# module_Rx_mux.net
KiCad netlist of a schematic drawn in EAGLE
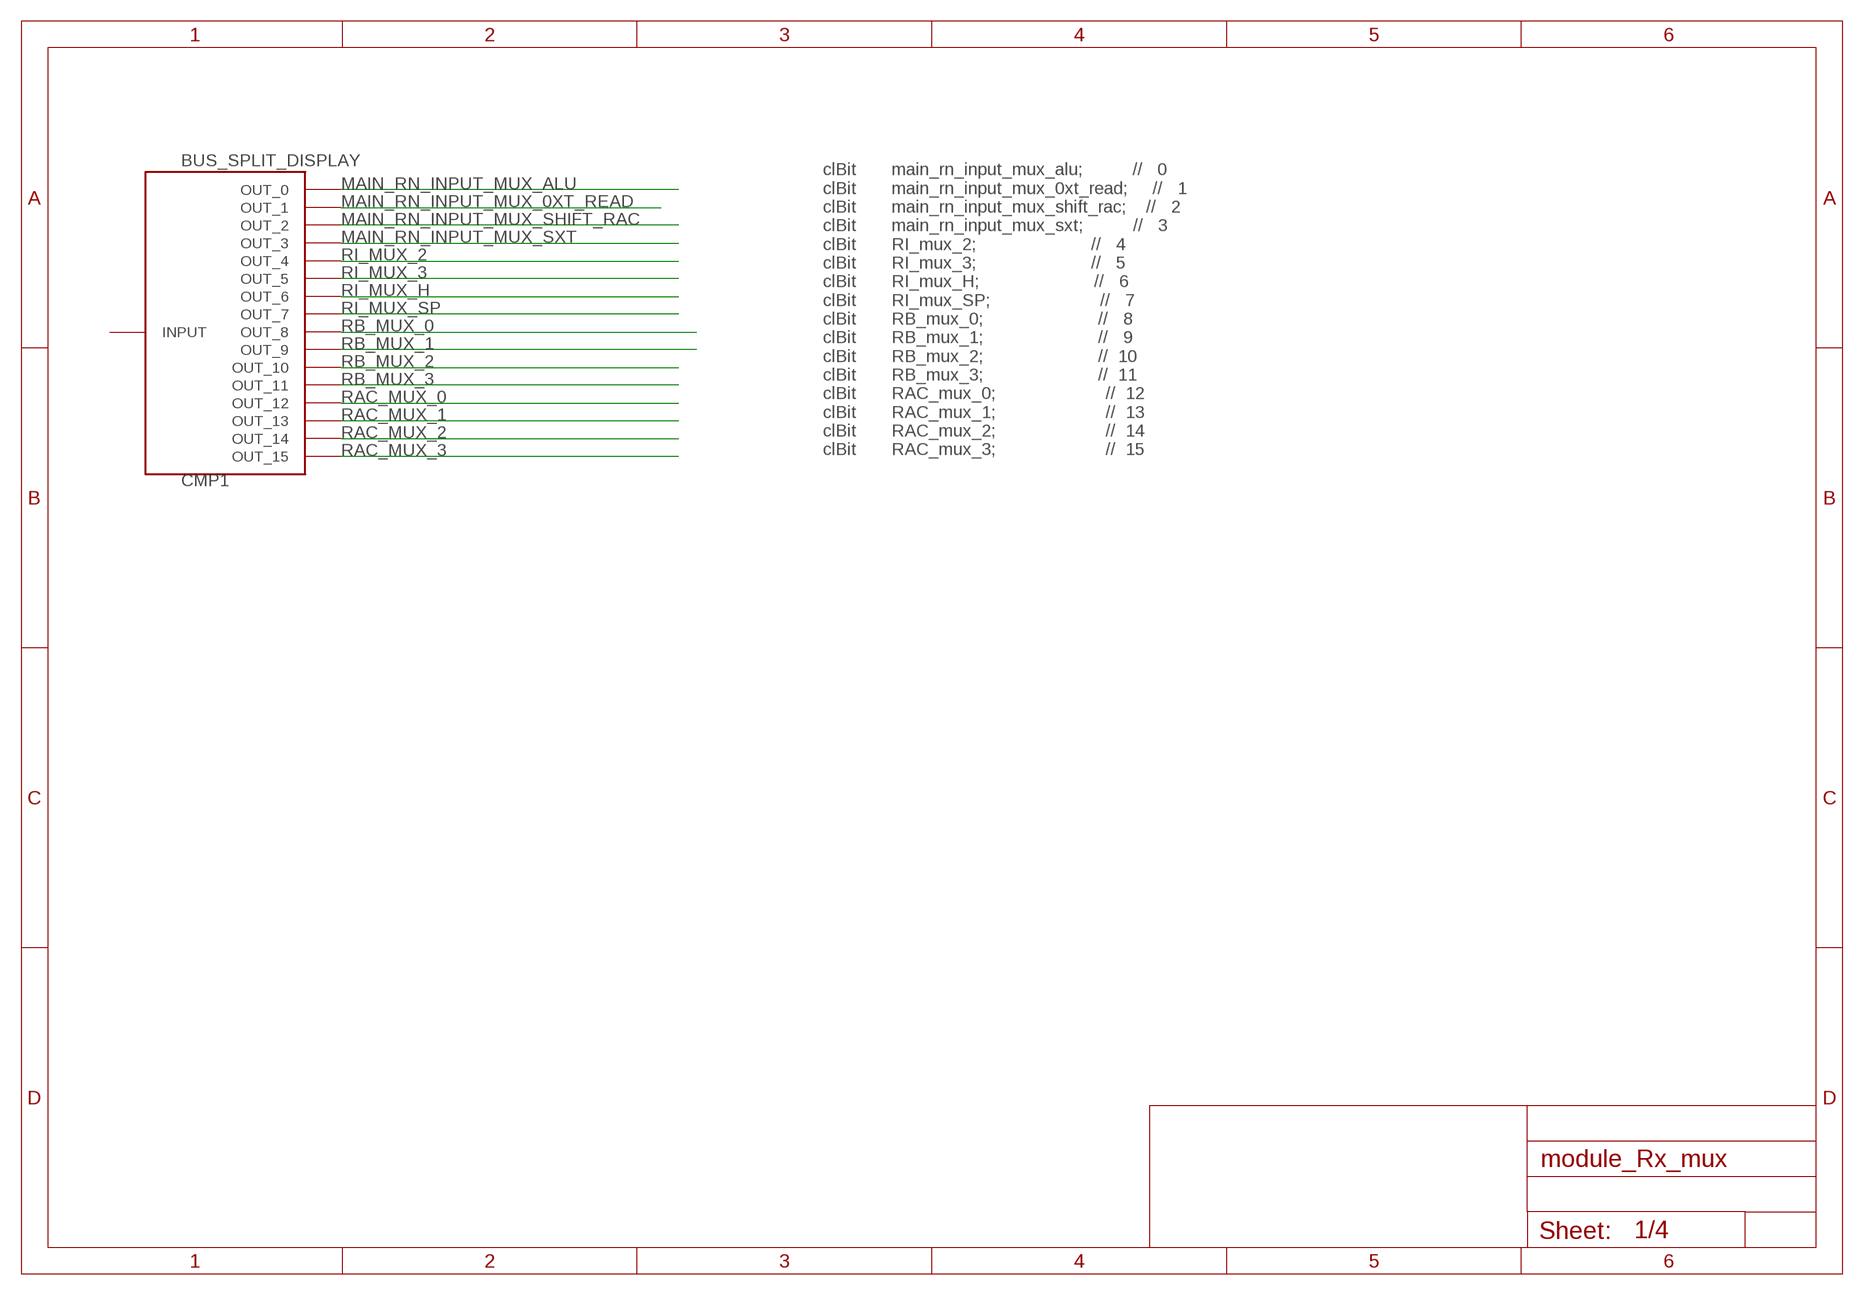
[diagram p0: schematic, sheet 1]
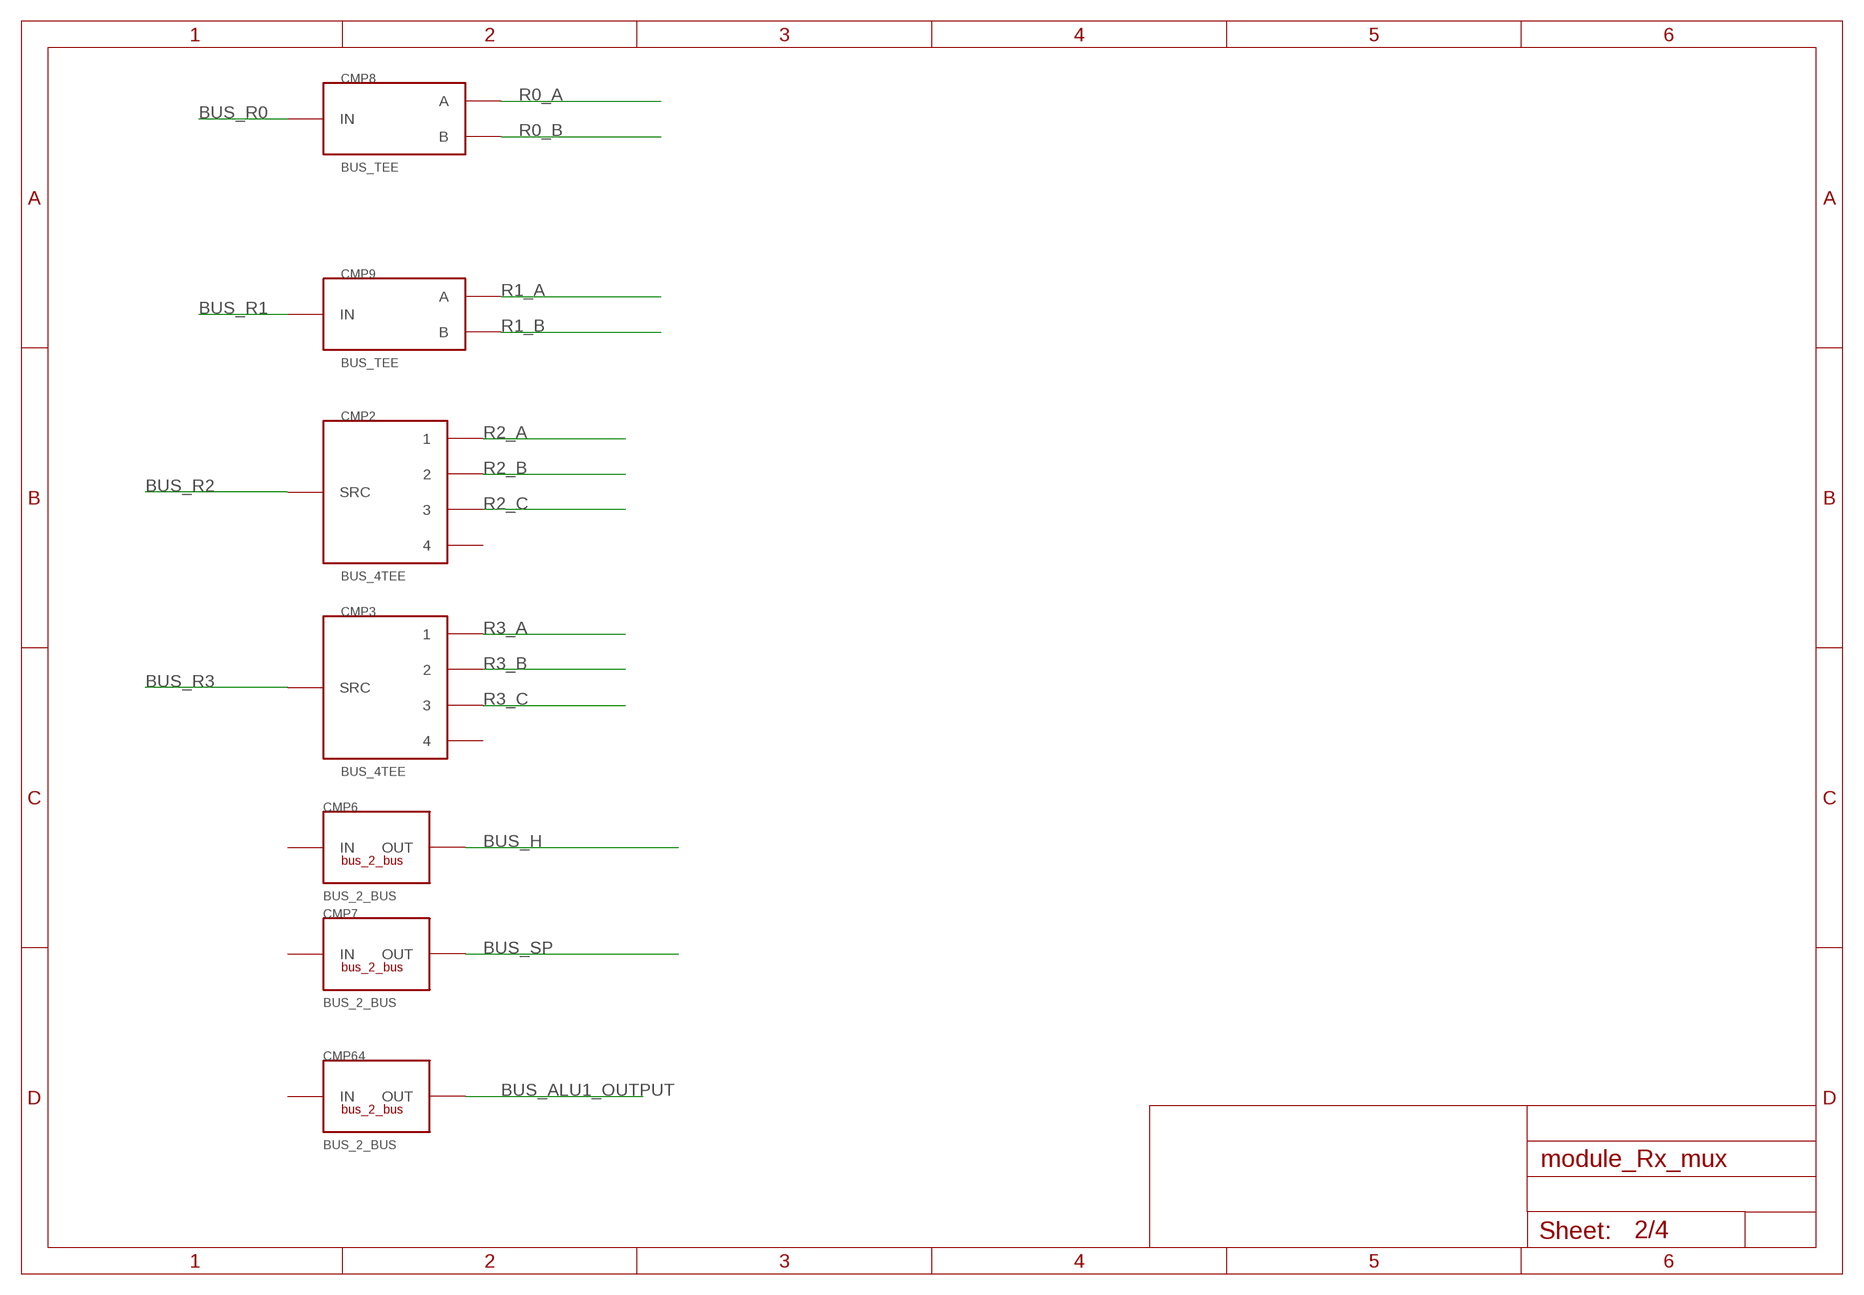
[diagram p1: schematic, sheet 2]
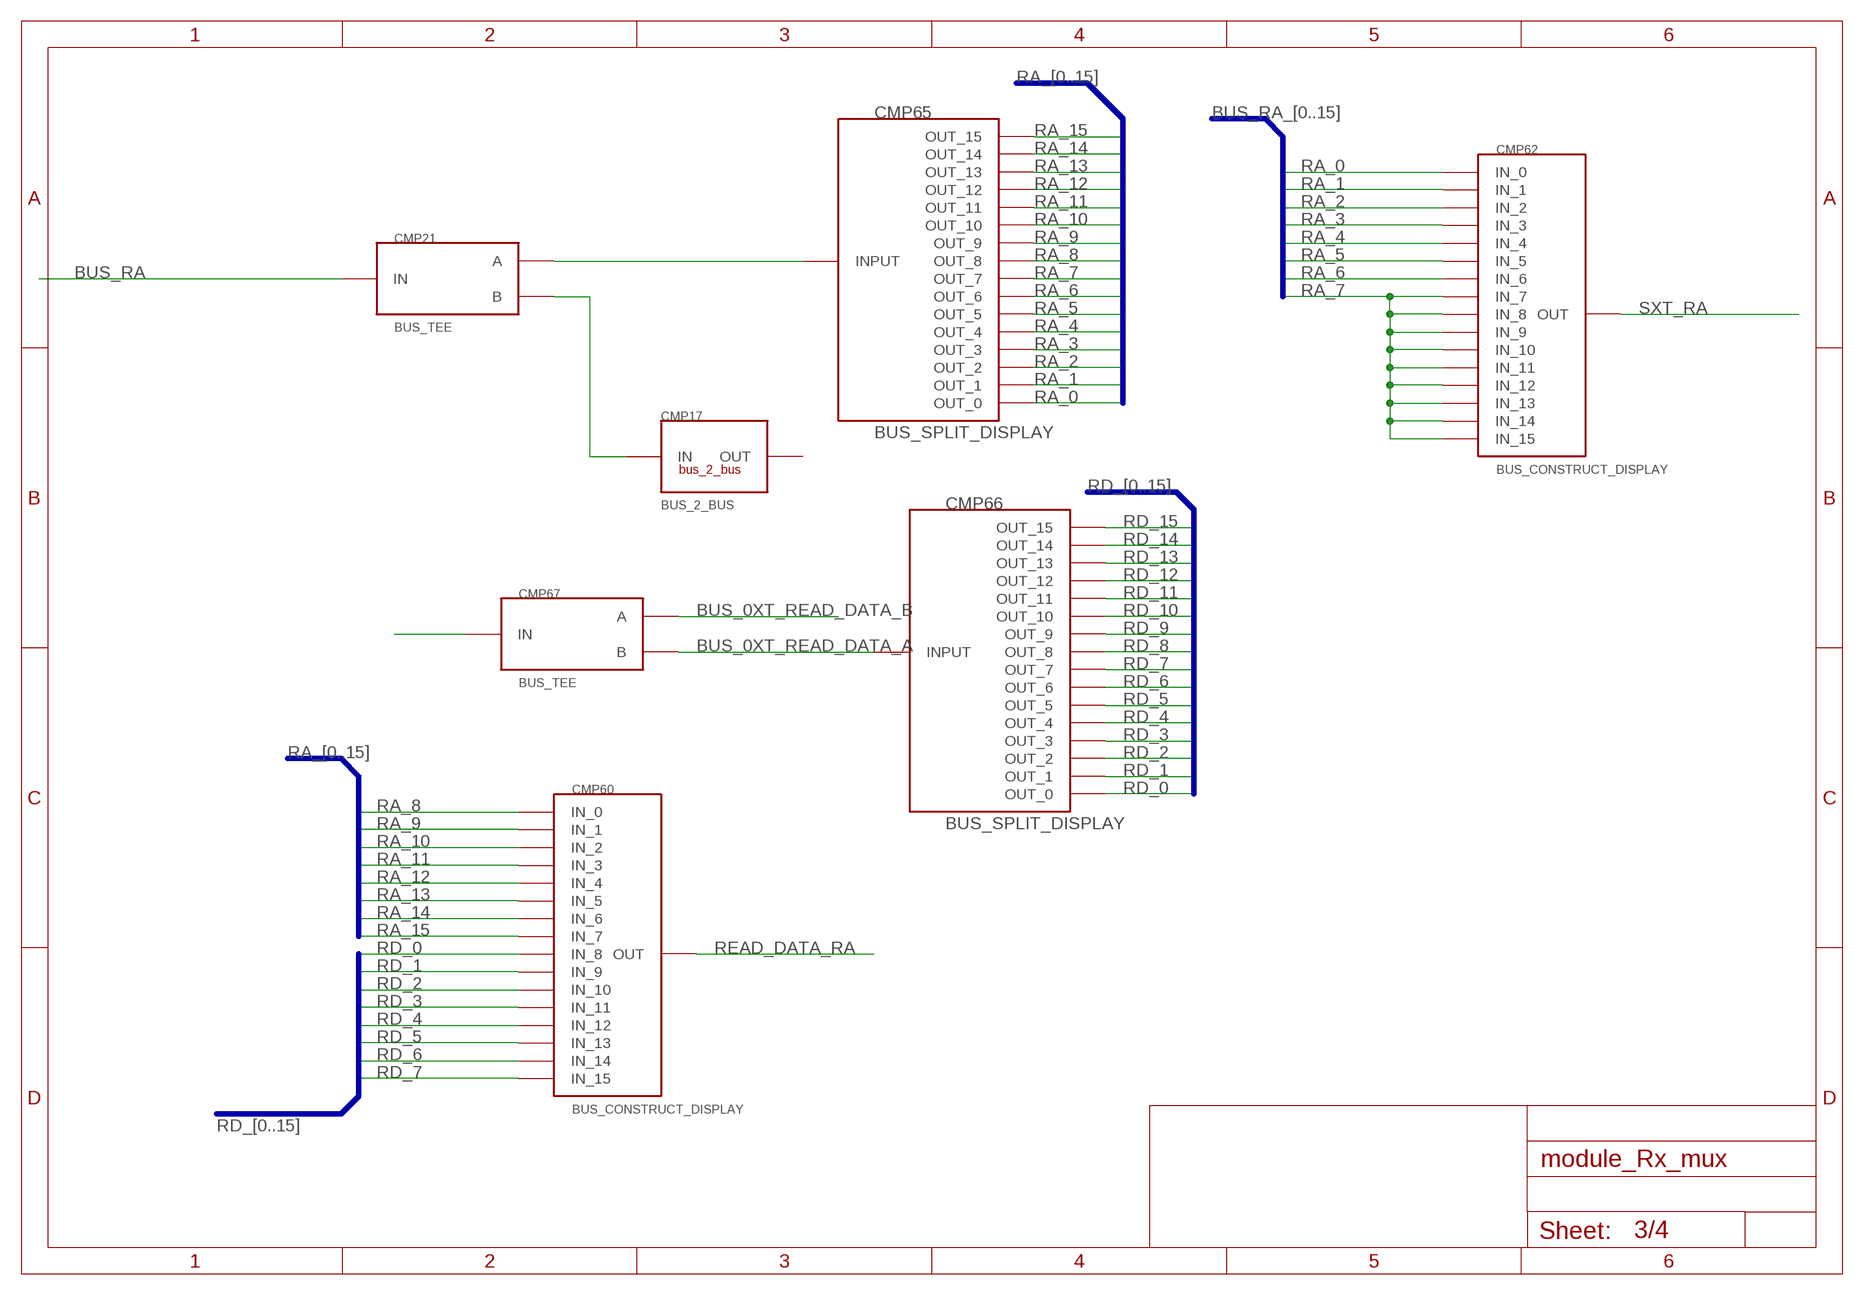
[diagram p2: schematic, sheet 3]
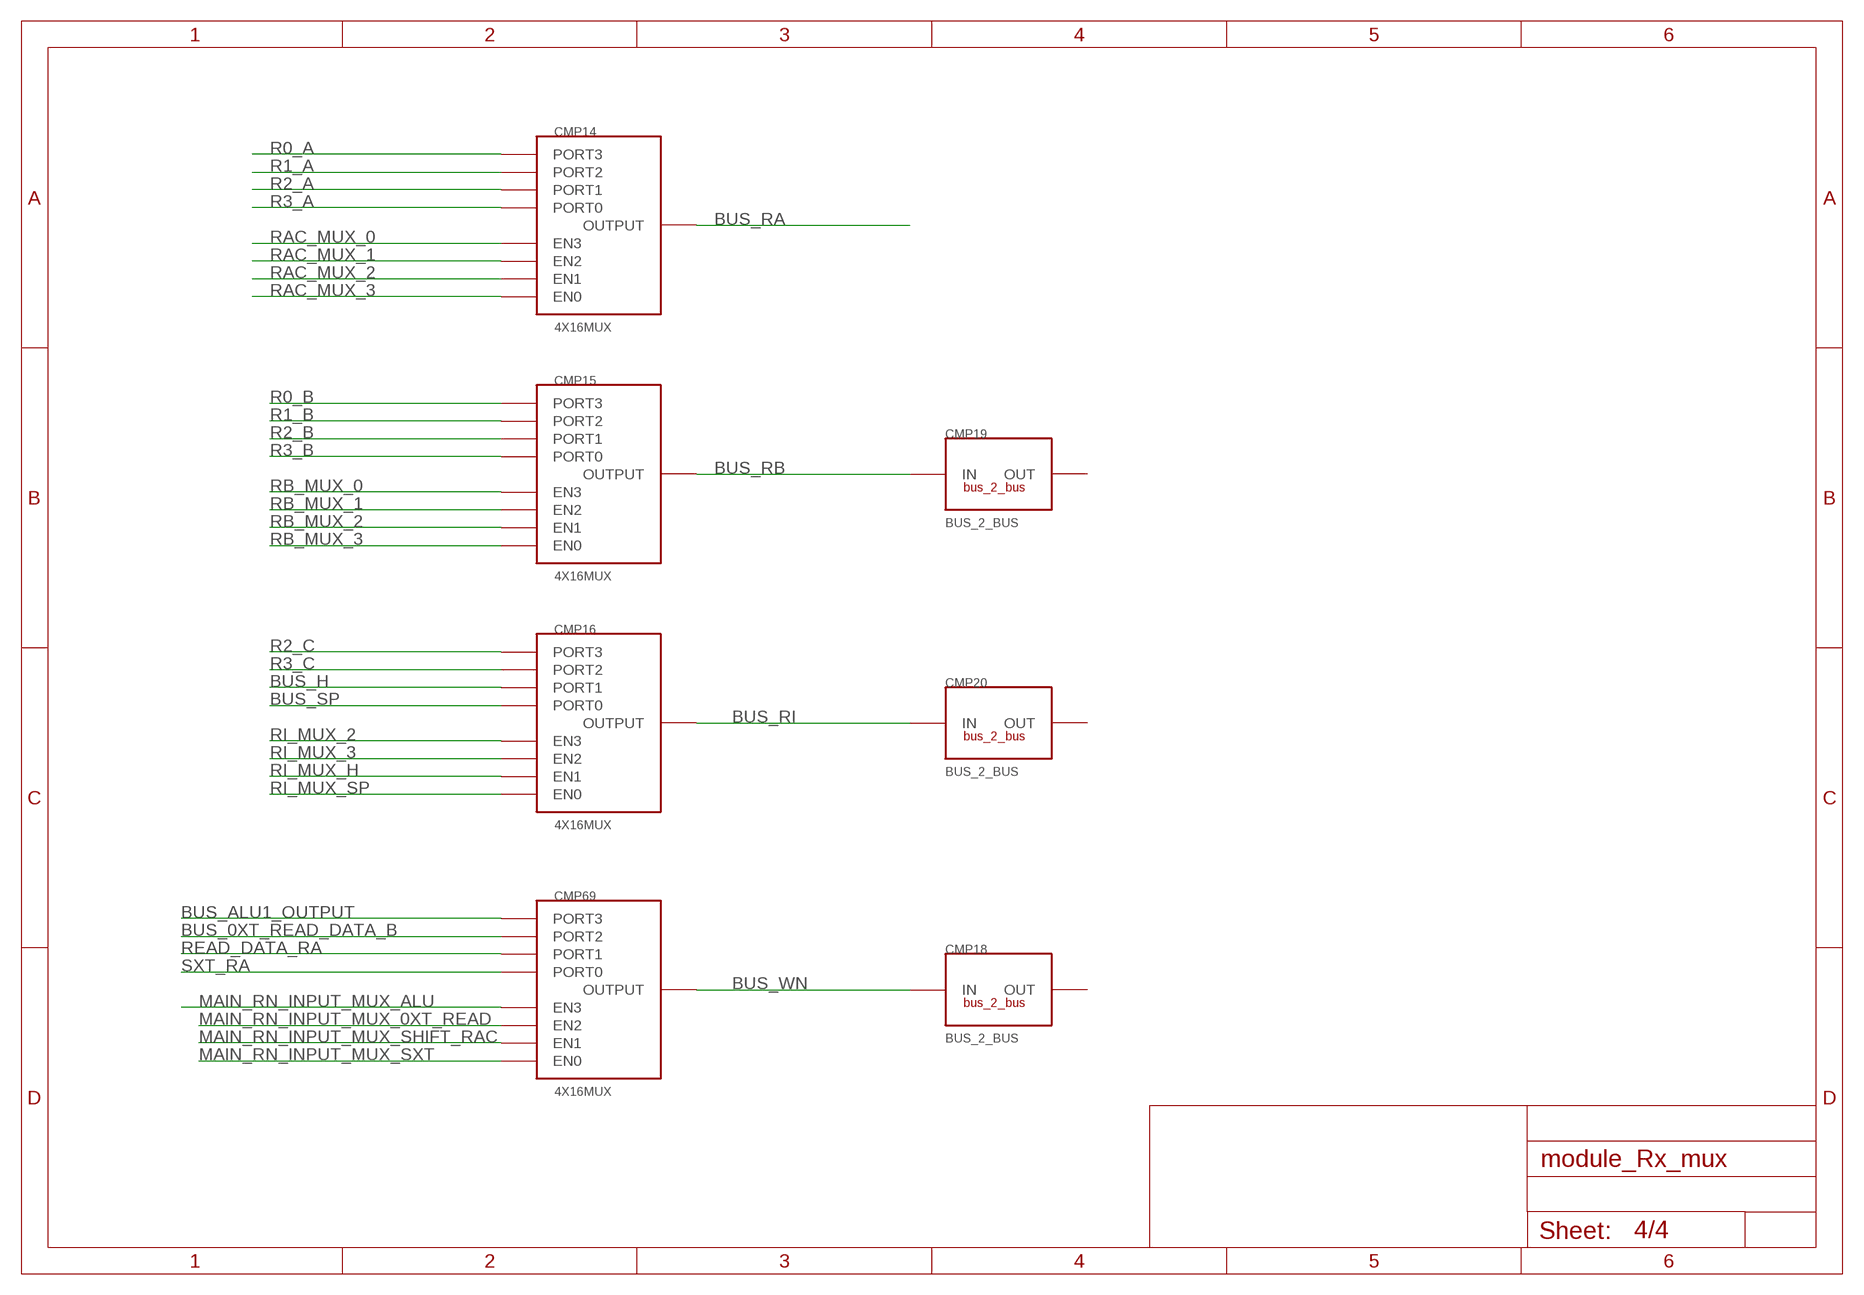
[diagram p3: schematic, sheet 4]

(export (version "E")
  (design (tool "Eeschema 10.0.6"))
  (components
    (comp (ref "CMP2")
      (value "BUS_4TEE")
      (footprint "eagle-import:BUS_4TEE")
      (libsource (lib "eagle-import") (part "BUS_4TEE"))
    )
    (comp (ref "CMP3")
      (value "BUS_4TEE")
      (footprint "eagle-import:BUS_4TEE")
      (libsource (lib "eagle-import") (part "BUS_4TEE"))
    )
    (comp (ref "CMP6")
      (value "BUS_2_BUS")
      (footprint "eagle-import:BUS2BUS")
      (libsource (lib "eagle-import") (part "BUS_2_BUS"))
    )
    (comp (ref "CMP7")
      (value "BUS_2_BUS")
      (footprint "eagle-import:BUS2BUS")
      (libsource (lib "eagle-import") (part "BUS_2_BUS"))
    )
    (comp (ref "CMP8")
      (value "BUS_TEE")
      (footprint "eagle-import:BUS_TEE")
      (libsource (lib "eagle-import") (part "BUS_TEE"))
    )
    (comp (ref "CMP9")
      (value "BUS_TEE")
      (footprint "eagle-import:BUS_TEE")
      (libsource (lib "eagle-import") (part "BUS_TEE"))
    )
    (comp (ref "CMP64")
      (value "BUS_2_BUS")
      (footprint "eagle-import:BUS2BUS")
      (libsource (lib "eagle-import") (part "BUS_2_BUS"))
    )
    (comp (ref "CMP17")
      (value "BUS_2_BUS")
      (footprint "eagle-import:BUS2BUS")
      (libsource (lib "eagle-import") (part "BUS_2_BUS"))
    )
    (comp (ref "CMP21")
      (value "BUS_TEE")
      (footprint "eagle-import:BUS_TEE")
      (libsource (lib "eagle-import") (part "BUS_TEE"))
    )
    (comp (ref "CMP60")
      (value "BUS_CONSTRUCT_DISPLAY")
      (footprint "eagle-import:BUS_SPLIT_DISPLAY")
      (libsource (lib "eagle-import") (part "BUS_CONSTRUCT_DISPLAY"))
    )
    (comp (ref "CMP62")
      (value "BUS_CONSTRUCT_DISPLAY")
      (footprint "eagle-import:BUS_SPLIT_DISPLAY")
      (libsource (lib "eagle-import") (part "BUS_CONSTRUCT_DISPLAY"))
    )
    (comp (ref "CMP65")
      (value "BUS_SPLIT_DISPLAY")
      (footprint "eagle-import:BUS_SPLIT_DISPLAY")
      (libsource (lib "eagle-import") (part "BUS_SPLIT_DISPLAY"))
    )
    (comp (ref "CMP66")
      (value "BUS_SPLIT_DISPLAY")
      (footprint "eagle-import:BUS_SPLIT_DISPLAY")
      (libsource (lib "eagle-import") (part "BUS_SPLIT_DISPLAY"))
    )
    (comp (ref "CMP67")
      (value "BUS_TEE")
      (footprint "eagle-import:BUS_TEE")
      (libsource (lib "eagle-import") (part "BUS_TEE"))
    )
    (comp (ref "CMP1")
      (value "BUS_SPLIT_DISPLAY")
      (footprint "eagle-import:BUS_SPLIT_DISPLAY")
      (libsource (lib "eagle-import") (part "BUS_SPLIT_DISPLAY"))
    )
    (comp (ref "CMP14")
      (value "4X16MUX")
      (footprint "eagle-import:4X16MUX")
      (libsource (lib "eagle-import") (part "4X16MUX"))
    )
    (comp (ref "CMP15")
      (value "4X16MUX")
      (footprint "eagle-import:4X16MUX")
      (libsource (lib "eagle-import") (part "4X16MUX"))
    )
    (comp (ref "CMP16")
      (value "4X16MUX")
      (footprint "eagle-import:4X16MUX")
      (libsource (lib "eagle-import") (part "4X16MUX"))
    )
    (comp (ref "CMP18")
      (value "BUS_2_BUS")
      (footprint "eagle-import:BUS2BUS")
      (libsource (lib "eagle-import") (part "BUS_2_BUS"))
    )
    (comp (ref "CMP19")
      (value "BUS_2_BUS")
      (footprint "eagle-import:BUS2BUS")
      (libsource (lib "eagle-import") (part "BUS_2_BUS"))
    )
    (comp (ref "CMP20")
      (value "BUS_2_BUS")
      (footprint "eagle-import:BUS2BUS")
      (libsource (lib "eagle-import") (part "BUS_2_BUS"))
    )
    (comp (ref "CMP69")
      (value "4X16MUX")
      (footprint "eagle-import:4X16MUX")
      (libsource (lib "eagle-import") (part "4X16MUX"))
    )
  )
  (nets
    (net (code "20") (name "BUS_0XT_READ_DATA_A") (class "Default")
      (node (ref "CMP66") (pin "INPUT") (pinfunction "INPUT_INPUT") (pintype "input"))
      (node (ref "CMP67") (pin "OUTB") (pinfunction "B_OUTB") (pintype "output"))
    )
    (net (code "21") (name "BUS_0XT_READ_DATA_B") (class "Default")
      (node (ref "CMP67") (pin "OUT_A") (pinfunction "A_OUT_A") (pintype "output"))
      (node (ref "CMP69") (pin "PORT2") (pinfunction "PORT2_PORT2") (pintype "input"))
    )
    (net (code "22") (name "BUS_ALU1_OUTPUT") (class "Default")
      (node (ref "CMP64") (pin "P$2") (pinfunction "OUT_P$2") (pintype "output"))
      (node (ref "CMP69") (pin "PORT3") (pinfunction "PORT3_PORT3") (pintype "input"))
    )
    (net (code "23") (name "BUS_H") (class "Default")
      (node (ref "CMP16") (pin "PORT1") (pinfunction "PORT1_PORT1") (pintype "input"))
      (node (ref "CMP6") (pin "P$2") (pinfunction "OUT_P$2") (pintype "output"))
    )
    (net (code "24") (name "BUS_R0") (class "Default")
      (node (ref "CMP8") (pin "INPUT") (pinfunction "IN_INPUT") (pintype "input"))
    )
    (net (code "25") (name "BUS_R1") (class "Default")
      (node (ref "CMP9") (pin "INPUT") (pinfunction "IN_INPUT") (pintype "input"))
    )
    (net (code "26") (name "BUS_R2") (class "Default")
      (node (ref "CMP2") (pin "SRC") (pinfunction "SRC_SRC") (pintype "input"))
    )
    (net (code "27") (name "BUS_R3") (class "Default")
      (node (ref "CMP3") (pin "SRC") (pinfunction "SRC_SRC") (pintype "input"))
    )
    (net (code "28") (name "BUS_RA") (class "Default")
      (node (ref "CMP14") (pin "PORTOUT") (pinfunction "OUTPUT_PORTOUT") (pintype "output"))
      (node (ref "CMP21") (pin "INPUT") (pinfunction "IN_INPUT") (pintype "input"))
    )
    (net (code "29") (name "BUS_RB") (class "Default")
      (node (ref "CMP15") (pin "PORTOUT") (pinfunction "OUTPUT_PORTOUT") (pintype "output"))
      (node (ref "CMP19") (pin "P$1") (pinfunction "IN_P$1") (pintype "input"))
    )
    (net (code "30") (name "BUS_RI") (class "Default")
      (node (ref "CMP16") (pin "PORTOUT") (pinfunction "OUTPUT_PORTOUT") (pintype "output"))
      (node (ref "CMP20") (pin "P$1") (pinfunction "IN_P$1") (pintype "input"))
    )
    (net (code "31") (name "BUS_SP") (class "Default")
      (node (ref "CMP16") (pin "PORT0") (pinfunction "PORT0_PORT0") (pintype "input"))
      (node (ref "CMP7") (pin "P$2") (pinfunction "OUT_P$2") (pintype "output"))
    )
    (net (code "32") (name "BUS_WN") (class "Default")
      (node (ref "CMP18") (pin "P$1") (pinfunction "IN_P$1") (pintype "input"))
      (node (ref "CMP69") (pin "PORTOUT") (pinfunction "OUTPUT_PORTOUT") (pintype "output"))
    )
    (net (code "33") (name "MAIN_RN_INPUT_MUX_0XT_READ") (class "Default")
      (node (ref "CMP1") (pin "P$2") (pinfunction "OUT_1_P$2") (pintype "output"))
      (node (ref "CMP69") (pin "EN2") (pinfunction "EN2_EN2") (pintype "input"))
    )
    (net (code "34") (name "MAIN_RN_INPUT_MUX_ALU") (class "Default")
      (node (ref "CMP1") (pin "P$1") (pinfunction "OUT_0_P$1") (pintype "output"))
      (node (ref "CMP69") (pin "EN3") (pinfunction "EN3_EN3") (pintype "input"))
    )
    (net (code "35") (name "MAIN_RN_INPUT_MUX_SHIFT_RAC") (class "Default")
      (node (ref "CMP1") (pin "P$3") (pinfunction "OUT_2_P$3") (pintype "output"))
      (node (ref "CMP69") (pin "EN1") (pinfunction "EN1_EN1") (pintype "input"))
    )
    (net (code "36") (name "MAIN_RN_INPUT_MUX_SXT") (class "Default")
      (node (ref "CMP1") (pin "P$4") (pinfunction "OUT_3_P$4") (pintype "output"))
      (node (ref "CMP69") (pin "EN0") (pinfunction "EN0_EN0") (pintype "input"))
    )
    (net (code "37") (name "Net-(CMP17-IN)") (class "Default")
      (node (ref "CMP17") (pin "P$1") (pinfunction "IN_P$1") (pintype "input"))
      (node (ref "CMP21") (pin "OUTB") (pinfunction "B_OUTB") (pintype "output"))
    )
    (net (code "38") (name "Net-(CMP21-A)") (class "Default")
      (node (ref "CMP21") (pin "OUT_A") (pinfunction "A_OUT_A") (pintype "output"))
      (node (ref "CMP65") (pin "INPUT") (pinfunction "INPUT_INPUT") (pintype "input"))
    )
    (net (code "39") (name "R0_A") (class "Default")
      (node (ref "CMP14") (pin "PORT3") (pinfunction "PORT3_PORT3") (pintype "input"))
      (node (ref "CMP8") (pin "OUT_A") (pinfunction "A_OUT_A") (pintype "output"))
    )
    (net (code "40") (name "R0_B") (class "Default")
      (node (ref "CMP15") (pin "PORT3") (pinfunction "PORT3_PORT3") (pintype "input"))
      (node (ref "CMP8") (pin "OUTB") (pinfunction "B_OUTB") (pintype "output"))
    )
    (net (code "41") (name "R1_A") (class "Default")
      (node (ref "CMP14") (pin "PORT2") (pinfunction "PORT2_PORT2") (pintype "input"))
      (node (ref "CMP9") (pin "OUT_A") (pinfunction "A_OUT_A") (pintype "output"))
    )
    (net (code "42") (name "R1_B") (class "Default")
      (node (ref "CMP15") (pin "PORT2") (pinfunction "PORT2_PORT2") (pintype "input"))
      (node (ref "CMP9") (pin "OUTB") (pinfunction "B_OUTB") (pintype "output"))
    )
    (net (code "43") (name "R2_A") (class "Default")
      (node (ref "CMP14") (pin "PORT1") (pinfunction "PORT1_PORT1") (pintype "input"))
      (node (ref "CMP2") (pin "1") (pinfunction "1_1") (pintype "output"))
    )
    (net (code "44") (name "R2_B") (class "Default")
      (node (ref "CMP15") (pin "PORT1") (pinfunction "PORT1_PORT1") (pintype "input"))
      (node (ref "CMP2") (pin "2") (pinfunction "2_2") (pintype "output"))
    )
    (net (code "45") (name "R2_C") (class "Default")
      (node (ref "CMP16") (pin "PORT3") (pinfunction "PORT3_PORT3") (pintype "input"))
      (node (ref "CMP2") (pin "3") (pinfunction "3_3") (pintype "output"))
    )
    (net (code "46") (name "R3_A") (class "Default")
      (node (ref "CMP14") (pin "PORT0") (pinfunction "PORT0_PORT0") (pintype "input"))
      (node (ref "CMP3") (pin "1") (pinfunction "1_1") (pintype "output"))
    )
    (net (code "47") (name "R3_B") (class "Default")
      (node (ref "CMP15") (pin "PORT0") (pinfunction "PORT0_PORT0") (pintype "input"))
      (node (ref "CMP3") (pin "2") (pinfunction "2_2") (pintype "output"))
    )
    (net (code "48") (name "R3_C") (class "Default")
      (node (ref "CMP16") (pin "PORT2") (pinfunction "PORT2_PORT2") (pintype "input"))
      (node (ref "CMP3") (pin "3") (pinfunction "3_3") (pintype "output"))
    )
    (net (code "49") (name "RAC_MUX_0") (class "Default")
      (node (ref "CMP1") (pin "P$13") (pinfunction "OUT_12_P$13") (pintype "output"))
      (node (ref "CMP14") (pin "EN3") (pinfunction "EN3_EN3") (pintype "input"))
    )
    (net (code "50") (name "RAC_MUX_1") (class "Default")
      (node (ref "CMP1") (pin "P$14") (pinfunction "OUT_13_P$14") (pintype "output"))
      (node (ref "CMP14") (pin "EN2") (pinfunction "EN2_EN2") (pintype "input"))
    )
    (net (code "51") (name "RAC_MUX_2") (class "Default")
      (node (ref "CMP1") (pin "P$15") (pinfunction "OUT_14_P$15") (pintype "output"))
      (node (ref "CMP14") (pin "EN1") (pinfunction "EN1_EN1") (pintype "input"))
    )
    (net (code "52") (name "RAC_MUX_3") (class "Default")
      (node (ref "CMP1") (pin "P$16") (pinfunction "OUT_15_P$16") (pintype "output"))
      (node (ref "CMP14") (pin "EN0") (pinfunction "EN0_EN0") (pintype "input"))
    )
    (net (code "53") (name "RA_0") (class "Default")
      (node (ref "CMP62") (pin "P$1") (pinfunction "IN_0_P$1") (pintype "input"))
      (node (ref "CMP65") (pin "P$1") (pinfunction "OUT_0_P$1") (pintype "output"))
    )
    (net (code "54") (name "RA_1") (class "Default")
      (node (ref "CMP62") (pin "P$2") (pinfunction "IN_1_P$2") (pintype "input"))
      (node (ref "CMP65") (pin "P$2") (pinfunction "OUT_1_P$2") (pintype "output"))
    )
    (net (code "55") (name "RA_2") (class "Default")
      (node (ref "CMP62") (pin "P$3") (pinfunction "IN_2_P$3") (pintype "input"))
      (node (ref "CMP65") (pin "P$3") (pinfunction "OUT_2_P$3") (pintype "output"))
    )
    (net (code "56") (name "RA_3") (class "Default")
      (node (ref "CMP62") (pin "P$4") (pinfunction "IN_3_P$4") (pintype "input"))
      (node (ref "CMP65") (pin "P$4") (pinfunction "OUT_3_P$4") (pintype "output"))
    )
    (net (code "57") (name "RA_4") (class "Default")
      (node (ref "CMP62") (pin "P$5") (pinfunction "IN_4_P$5") (pintype "input"))
      (node (ref "CMP65") (pin "P$5") (pinfunction "OUT_4_P$5") (pintype "output"))
    )
    (net (code "58") (name "RA_5") (class "Default")
      (node (ref "CMP62") (pin "P$6") (pinfunction "IN_5_P$6") (pintype "input"))
      (node (ref "CMP65") (pin "P$6") (pinfunction "OUT_5_P$6") (pintype "output"))
    )
    (net (code "59") (name "RA_6") (class "Default")
      (node (ref "CMP62") (pin "P$7") (pinfunction "IN_6_P$7") (pintype "input"))
      (node (ref "CMP65") (pin "P$7") (pinfunction "OUT_6_P$7") (pintype "output"))
    )
    (net (code "60") (name "RA_7") (class "Default")
      (node (ref "CMP62") (pin "P$10") (pinfunction "IN_9_P$10") (pintype "input"))
      (node (ref "CMP62") (pin "P$11") (pinfunction "IN_10_P$11") (pintype "input"))
      (node (ref "CMP62") (pin "P$12") (pinfunction "IN_11_P$12") (pintype "input"))
      (node (ref "CMP62") (pin "P$13") (pinfunction "IN_12_P$13") (pintype "input"))
      (node (ref "CMP62") (pin "P$14") (pinfunction "IN_13_P$14") (pintype "input"))
      (node (ref "CMP62") (pin "P$15") (pinfunction "IN_14_P$15") (pintype "input"))
      (node (ref "CMP62") (pin "P$16") (pinfunction "IN_15_P$16") (pintype "input"))
      (node (ref "CMP62") (pin "P$8") (pinfunction "IN_7_P$8") (pintype "input"))
      (node (ref "CMP62") (pin "P$9") (pinfunction "IN_8_P$9") (pintype "input"))
      (node (ref "CMP65") (pin "P$8") (pinfunction "OUT_7_P$8") (pintype "output"))
    )
    (net (code "61") (name "RA_8") (class "Default")
      (node (ref "CMP60") (pin "P$1") (pinfunction "IN_0_P$1") (pintype "input"))
      (node (ref "CMP65") (pin "P$9") (pinfunction "OUT_8_P$9") (pintype "output"))
    )
    (net (code "62") (name "RA_9") (class "Default")
      (node (ref "CMP60") (pin "P$2") (pinfunction "IN_1_P$2") (pintype "input"))
      (node (ref "CMP65") (pin "P$10") (pinfunction "OUT_9_P$10") (pintype "output"))
    )
    (net (code "63") (name "RA_10") (class "Default")
      (node (ref "CMP60") (pin "P$3") (pinfunction "IN_2_P$3") (pintype "input"))
      (node (ref "CMP65") (pin "P$11") (pinfunction "OUT_10_P$11") (pintype "output"))
    )
    (net (code "64") (name "RA_11") (class "Default")
      (node (ref "CMP60") (pin "P$4") (pinfunction "IN_3_P$4") (pintype "input"))
      (node (ref "CMP65") (pin "P$12") (pinfunction "OUT_11_P$12") (pintype "output"))
    )
    (net (code "65") (name "RA_12") (class "Default")
      (node (ref "CMP60") (pin "P$5") (pinfunction "IN_4_P$5") (pintype "input"))
      (node (ref "CMP65") (pin "P$13") (pinfunction "OUT_12_P$13") (pintype "output"))
    )
    (net (code "66") (name "RA_13") (class "Default")
      (node (ref "CMP60") (pin "P$6") (pinfunction "IN_5_P$6") (pintype "input"))
      (node (ref "CMP65") (pin "P$14") (pinfunction "OUT_13_P$14") (pintype "output"))
    )
    (net (code "67") (name "RA_14") (class "Default")
      (node (ref "CMP60") (pin "P$7") (pinfunction "IN_6_P$7") (pintype "input"))
      (node (ref "CMP65") (pin "P$15") (pinfunction "OUT_14_P$15") (pintype "output"))
    )
    (net (code "68") (name "RA_15") (class "Default")
      (node (ref "CMP60") (pin "P$8") (pinfunction "IN_7_P$8") (pintype "input"))
      (node (ref "CMP65") (pin "P$16") (pinfunction "OUT_15_P$16") (pintype "output"))
    )
    (net (code "69") (name "RB_MUX_0") (class "Default")
      (node (ref "CMP1") (pin "P$9") (pinfunction "OUT_8_P$9") (pintype "output"))
      (node (ref "CMP15") (pin "EN3") (pinfunction "EN3_EN3") (pintype "input"))
    )
    (net (code "70") (name "RB_MUX_1") (class "Default")
      (node (ref "CMP1") (pin "P$10") (pinfunction "OUT_9_P$10") (pintype "output"))
      (node (ref "CMP15") (pin "EN2") (pinfunction "EN2_EN2") (pintype "input"))
    )
    (net (code "71") (name "RB_MUX_2") (class "Default")
      (node (ref "CMP1") (pin "P$11") (pinfunction "OUT_10_P$11") (pintype "output"))
      (node (ref "CMP15") (pin "EN1") (pinfunction "EN1_EN1") (pintype "input"))
    )
    (net (code "72") (name "RB_MUX_3") (class "Default")
      (node (ref "CMP1") (pin "P$12") (pinfunction "OUT_11_P$12") (pintype "output"))
      (node (ref "CMP15") (pin "EN0") (pinfunction "EN0_EN0") (pintype "input"))
    )
    (net (code "73") (name "RD_0") (class "Default")
      (node (ref "CMP60") (pin "P$9") (pinfunction "IN_8_P$9") (pintype "input"))
      (node (ref "CMP66") (pin "P$1") (pinfunction "OUT_0_P$1") (pintype "output"))
    )
    (net (code "74") (name "RD_1") (class "Default")
      (node (ref "CMP60") (pin "P$10") (pinfunction "IN_9_P$10") (pintype "input"))
      (node (ref "CMP66") (pin "P$2") (pinfunction "OUT_1_P$2") (pintype "output"))
    )
    (net (code "75") (name "RD_2") (class "Default")
      (node (ref "CMP60") (pin "P$11") (pinfunction "IN_10_P$11") (pintype "input"))
      (node (ref "CMP66") (pin "P$3") (pinfunction "OUT_2_P$3") (pintype "output"))
    )
    (net (code "76") (name "RD_3") (class "Default")
      (node (ref "CMP60") (pin "P$12") (pinfunction "IN_11_P$12") (pintype "input"))
      (node (ref "CMP66") (pin "P$4") (pinfunction "OUT_3_P$4") (pintype "output"))
    )
    (net (code "77") (name "RD_4") (class "Default")
      (node (ref "CMP60") (pin "P$13") (pinfunction "IN_12_P$13") (pintype "input"))
      (node (ref "CMP66") (pin "P$5") (pinfunction "OUT_4_P$5") (pintype "output"))
    )
    (net (code "78") (name "RD_5") (class "Default")
      (node (ref "CMP60") (pin "P$14") (pinfunction "IN_13_P$14") (pintype "input"))
      (node (ref "CMP66") (pin "P$6") (pinfunction "OUT_5_P$6") (pintype "output"))
    )
    (net (code "79") (name "RD_6") (class "Default")
      (node (ref "CMP60") (pin "P$15") (pinfunction "IN_14_P$15") (pintype "input"))
      (node (ref "CMP66") (pin "P$7") (pinfunction "OUT_6_P$7") (pintype "output"))
    )
    (net (code "80") (name "RD_7") (class "Default")
      (node (ref "CMP60") (pin "P$16") (pinfunction "IN_15_P$16") (pintype "input"))
      (node (ref "CMP66") (pin "P$8") (pinfunction "OUT_7_P$8") (pintype "output"))
    )
    (net (code "81") (name "RD_8") (class "Default")
      (node (ref "CMP66") (pin "P$9") (pinfunction "OUT_8_P$9") (pintype "output"))
    )
    (net (code "82") (name "RD_9") (class "Default")
      (node (ref "CMP66") (pin "P$10") (pinfunction "OUT_9_P$10") (pintype "output"))
    )
    (net (code "83") (name "RD_10") (class "Default")
      (node (ref "CMP66") (pin "P$11") (pinfunction "OUT_10_P$11") (pintype "output"))
    )
    (net (code "84") (name "RD_11") (class "Default")
      (node (ref "CMP66") (pin "P$12") (pinfunction "OUT_11_P$12") (pintype "output"))
    )
    (net (code "85") (name "RD_12") (class "Default")
      (node (ref "CMP66") (pin "P$13") (pinfunction "OUT_12_P$13") (pintype "output"))
    )
    (net (code "86") (name "RD_13") (class "Default")
      (node (ref "CMP66") (pin "P$14") (pinfunction "OUT_13_P$14") (pintype "output"))
    )
    (net (code "87") (name "RD_14") (class "Default")
      (node (ref "CMP66") (pin "P$15") (pinfunction "OUT_14_P$15") (pintype "output"))
    )
    (net (code "88") (name "RD_15") (class "Default")
      (node (ref "CMP66") (pin "P$16") (pinfunction "OUT_15_P$16") (pintype "output"))
    )
    (net (code "89") (name "READ_DATA_RA") (class "Default")
      (node (ref "CMP60") (pin "INPUT") (pinfunction "OUT_INPUT") (pintype "output"))
      (node (ref "CMP69") (pin "PORT1") (pinfunction "PORT1_PORT1") (pintype "input"))
    )
    (net (code "90") (name "RI_MUX_2") (class "Default")
      (node (ref "CMP1") (pin "P$5") (pinfunction "OUT_4_P$5") (pintype "output"))
      (node (ref "CMP16") (pin "EN3") (pinfunction "EN3_EN3") (pintype "input"))
    )
    (net (code "91") (name "RI_MUX_3") (class "Default")
      (node (ref "CMP1") (pin "P$6") (pinfunction "OUT_5_P$6") (pintype "output"))
      (node (ref "CMP16") (pin "EN2") (pinfunction "EN2_EN2") (pintype "input"))
    )
    (net (code "92") (name "RI_MUX_H") (class "Default")
      (node (ref "CMP1") (pin "P$7") (pinfunction "OUT_6_P$7") (pintype "output"))
      (node (ref "CMP16") (pin "EN1") (pinfunction "EN1_EN1") (pintype "input"))
    )
    (net (code "93") (name "RI_MUX_SP") (class "Default")
      (node (ref "CMP1") (pin "P$8") (pinfunction "OUT_7_P$8") (pintype "output"))
      (node (ref "CMP16") (pin "EN0") (pinfunction "EN0_EN0") (pintype "input"))
    )
    (net (code "94") (name "SXT_RA") (class "Default")
      (node (ref "CMP62") (pin "INPUT") (pinfunction "OUT_INPUT") (pintype "output"))
      (node (ref "CMP69") (pin "PORT0") (pinfunction "PORT0_PORT0") (pintype "input"))
    )
    (net (code "95") (name "unconnected-(CMP1-PadINPUT)") (class "Default")
      (node (ref "CMP1") (pin "INPUT") (pinfunction "INPUT_INPUT") (pintype "input"))
    )
    (net (code "96") (name "unconnected-(CMP2-Pad4)") (class "Default")
      (node (ref "CMP2") (pin "4") (pinfunction "4_4") (pintype "output"))
    )
    (net (code "97") (name "unconnected-(CMP3-Pad4)") (class "Default")
      (node (ref "CMP3") (pin "4") (pinfunction "4_4") (pintype "output"))
    )
    (net (code "98") (name "unconnected-(CMP6-IN-PadP$1)") (class "Default")
      (node (ref "CMP6") (pin "P$1") (pinfunction "IN_P$1") (pintype "input"))
    )
    (net (code "99") (name "unconnected-(CMP7-IN-PadP$1)") (class "Default")
      (node (ref "CMP7") (pin "P$1") (pinfunction "IN_P$1") (pintype "input"))
    )
    (net (code "100") (name "unconnected-(CMP17-OUT-PadP$2)") (class "Default")
      (node (ref "CMP17") (pin "P$2") (pinfunction "OUT_P$2") (pintype "output"))
    )
    (net (code "101") (name "unconnected-(CMP18-OUT-PadP$2)") (class "Default")
      (node (ref "CMP18") (pin "P$2") (pinfunction "OUT_P$2") (pintype "output"))
    )
    (net (code "102") (name "unconnected-(CMP19-OUT-PadP$2)") (class "Default")
      (node (ref "CMP19") (pin "P$2") (pinfunction "OUT_P$2") (pintype "output"))
    )
    (net (code "103") (name "unconnected-(CMP20-OUT-PadP$2)") (class "Default")
      (node (ref "CMP20") (pin "P$2") (pinfunction "OUT_P$2") (pintype "output"))
    )
    (net (code "104") (name "unconnected-(CMP64-IN-PadP$1)") (class "Default")
      (node (ref "CMP64") (pin "P$1") (pinfunction "IN_P$1") (pintype "input"))
    )
    (net (code "105") (name "unconnected-(CMP67-IN-PadINPUT)") (class "Default")
      (node (ref "CMP67") (pin "INPUT") (pinfunction "IN_INPUT") (pintype "input"))
    )
  )
)
